# I2C_Servo_v2.net
KiCad netlist of a schematic drawn in EAGLE
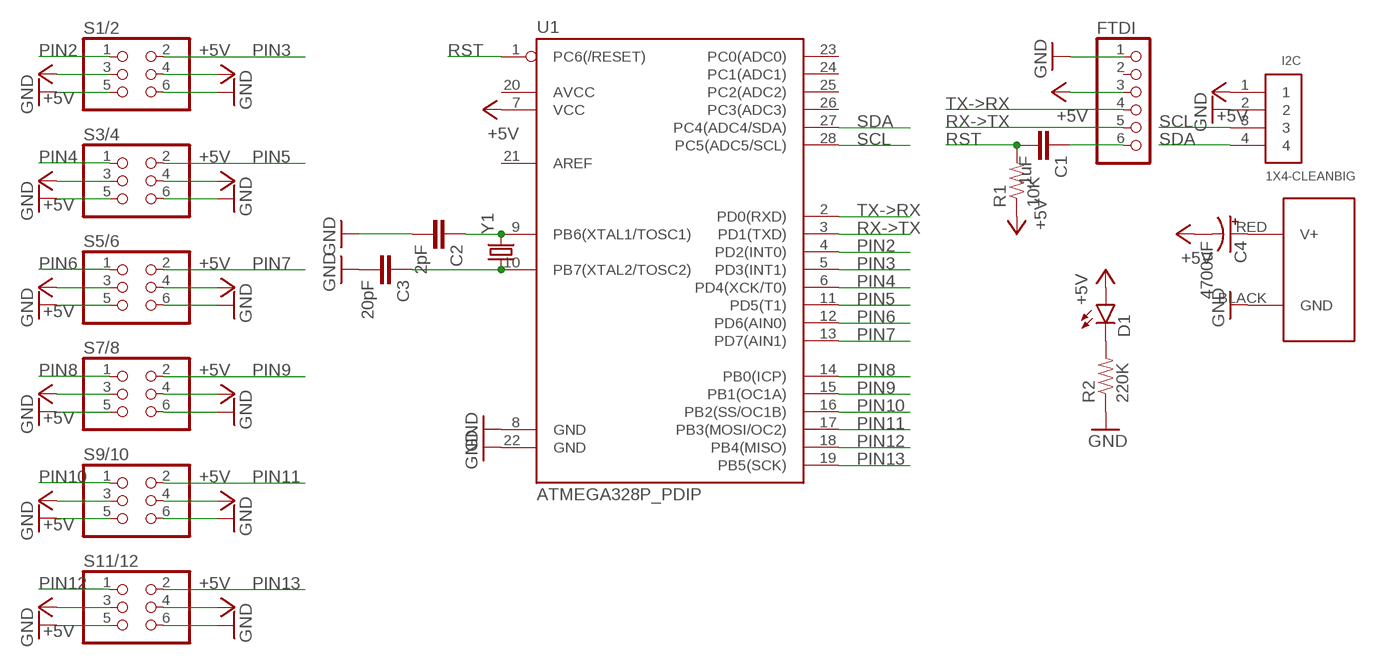
[diagram p0: schematic, sheet 1]

(export (version "E")
  (design (tool "Eeschema 10.0.6"))
  (components
    (comp (ref "C1")
      (value ".1uF")
      (footprint "eagle-import:CAP-PTH-SMALL")
      (libsource (lib "eagle-import") (part "CAPPTH"))
    )
    (comp (ref "C2")
      (value "2pF")
      (footprint "eagle-import:CAP-PTH-SMALL")
      (libsource (lib "eagle-import") (part "CAPPTH"))
    )
    (comp (ref "C3")
      (value "20pF")
      (footprint "eagle-import:CAP-PTH-SMALL")
      (libsource (lib "eagle-import") (part "CAPPTH"))
    )
    (comp (ref "C4")
      (value "4700uF")
      (footprint "eagle-import:E5-13")
      (libsource (lib "eagle-import") (part "CPOL-USE5-13"))
    )
    (comp (ref "D1")
      (value "LED3MM")
      (footprint "eagle-import:LED3MM")
      (libsource (lib "eagle-import") (part "LED3MM"))
    )
    (comp (ref "FTDI")
      (value "PINHD-1X6CLEAN")
      (footprint "eagle-import:1X06-CLEAN")
      (libsource (lib "eagle-import") (part "PINHD-1X6CLEAN"))
    )
    (comp (ref "I2C")
      (value "1X4-CLEANBIG")
      (footprint "eagle-import:1X04-CLEANBIG")
      (libsource (lib "eagle-import") (part "1X4-CLEANBIG"))
    )
    (comp (ref "J1")
      (value "POWERPOLE_POWER25A_HORIZONTAL_G2")
      (footprint "eagle-import:POWERPOLE_PAIR_25A_HORIZ_G2")
      (libsource (lib "eagle-import") (part "POWERPOLE_POWER25A_HORIZONTAL_G2"))
    )
    (comp (ref "R1")
      (value "10K")
      (footprint "eagle-import:AXIAL-0.3")
      (libsource (lib "eagle-import") (part "RESISTORAXIAL-0.3"))
    )
    (comp (ref "R2")
      (value "220K")
      (footprint "eagle-import:AXIAL-0.3")
      (libsource (lib "eagle-import") (part "RESISTORAXIAL-0.3"))
    )
    (comp (ref "S1/2")
      (value "PINHD-2X3")
      (footprint "eagle-import:2X03")
      (libsource (lib "eagle-import") (part "PINHD-2X3"))
    )
    (comp (ref "S3/4")
      (value "PINHD-2X3")
      (footprint "eagle-import:2X03")
      (libsource (lib "eagle-import") (part "PINHD-2X3"))
    )
    (comp (ref "S5/6")
      (value "PINHD-2X3")
      (footprint "eagle-import:2X03")
      (libsource (lib "eagle-import") (part "PINHD-2X3"))
    )
    (comp (ref "S7/8")
      (value "PINHD-2X3")
      (footprint "eagle-import:2X03")
      (libsource (lib "eagle-import") (part "PINHD-2X3"))
    )
    (comp (ref "S9/10")
      (value "PINHD-2X3")
      (footprint "eagle-import:2X03")
      (libsource (lib "eagle-import") (part "PINHD-2X3"))
    )
    (comp (ref "S11/12")
      (value "PINHD-2X3")
      (footprint "eagle-import:2X03")
      (libsource (lib "eagle-import") (part "PINHD-2X3"))
    )
    (comp (ref "U1")
      (value "ATMEGA328P_PDIP")
      (footprint "eagle-import:DIL28-3")
      (libsource (lib "eagle-import") (part "ATMEGA328P_PDIP"))
    )
    (comp (ref "Y1")
      (value "CRYSTALHC49US")
      (footprint "eagle-import:HC49US")
      (libsource (lib "eagle-import") (part "CRYSTALHC49US"))
    )
  )
  (nets
    (net (code "1") (name "+5V") (class "Default")
      (node (ref "C4") (pin "-") (pinfunction "-_-") (pintype "passive"))
      (node (ref "D1") (pin "A") (pinfunction "A_A") (pintype "passive"))
      (node (ref "FTDI") (pin "3") (pinfunction "3_3") (pintype "passive"))
      (node (ref "I2C") (pin "1") (pinfunction "1_1") (pintype "bidirectional"))
      (node (ref "R1") (pin "P$1") (pinfunction "1_P$1") (pintype "passive"))
      (node (ref "S1/2") (pin "3") (pinfunction "3_3") (pintype "passive"))
      (node (ref "S1/2") (pin "4") (pinfunction "4_4") (pintype "passive"))
      (node (ref "S11/12") (pin "3") (pinfunction "3_3") (pintype "passive"))
      (node (ref "S11/12") (pin "4") (pinfunction "4_4") (pintype "passive"))
      (node (ref "S3/4") (pin "3") (pinfunction "3_3") (pintype "passive"))
      (node (ref "S3/4") (pin "4") (pinfunction "4_4") (pintype "passive"))
      (node (ref "S5/6") (pin "3") (pinfunction "3_3") (pintype "passive"))
      (node (ref "S5/6") (pin "4") (pinfunction "4_4") (pintype "passive"))
      (node (ref "S7/8") (pin "3") (pinfunction "3_3") (pintype "passive"))
      (node (ref "S7/8") (pin "4") (pinfunction "4_4") (pintype "passive"))
      (node (ref "S9/10") (pin "3") (pinfunction "3_3") (pintype "passive"))
      (node (ref "S9/10") (pin "4") (pinfunction "4_4") (pintype "passive"))
      (node (ref "U1") (pin "7") (pinfunction "VCC_7") (pintype "bidirectional"))
    )
    (net (code "2") (name "/PIN2") (class "Default")
      (node (ref "S1/2") (pin "1") (pinfunction "1_1") (pintype "passive"))
      (node (ref "U1") (pin "4") (pinfunction "PD2(INT0)_4") (pintype "bidirectional"))
    )
    (net (code "3") (name "/PIN3") (class "Default")
      (node (ref "S1/2") (pin "2") (pinfunction "2_2") (pintype "passive"))
      (node (ref "U1") (pin "5") (pinfunction "PD3(INT1)_5") (pintype "bidirectional"))
    )
    (net (code "4") (name "/PIN4") (class "Default")
      (node (ref "S3/4") (pin "1") (pinfunction "1_1") (pintype "passive"))
      (node (ref "U1") (pin "6") (pinfunction "PD4(XCK/T0)_6") (pintype "bidirectional"))
    )
    (net (code "5") (name "/PIN5") (class "Default")
      (node (ref "S3/4") (pin "2") (pinfunction "2_2") (pintype "passive"))
      (node (ref "U1") (pin "11") (pinfunction "PD5(T1)_11") (pintype "bidirectional"))
    )
    (net (code "6") (name "/PIN6") (class "Default")
      (node (ref "S5/6") (pin "1") (pinfunction "1_1") (pintype "passive"))
      (node (ref "U1") (pin "12") (pinfunction "PD6(AIN0)_12") (pintype "bidirectional"))
    )
    (net (code "7") (name "/PIN7") (class "Default")
      (node (ref "S5/6") (pin "2") (pinfunction "2_2") (pintype "passive"))
      (node (ref "U1") (pin "13") (pinfunction "PD7(AIN1)_13") (pintype "bidirectional"))
    )
    (net (code "8") (name "/PIN8") (class "Default")
      (node (ref "S7/8") (pin "1") (pinfunction "1_1") (pintype "passive"))
      (node (ref "U1") (pin "14") (pinfunction "PB0(ICP)_14") (pintype "bidirectional"))
    )
    (net (code "9") (name "/PIN9") (class "Default")
      (node (ref "S7/8") (pin "2") (pinfunction "2_2") (pintype "passive"))
      (node (ref "U1") (pin "15") (pinfunction "PB1(OC1A)_15") (pintype "bidirectional"))
    )
    (net (code "10") (name "/PIN10") (class "Default")
      (node (ref "S9/10") (pin "1") (pinfunction "1_1") (pintype "passive"))
      (node (ref "U1") (pin "16") (pinfunction "PB2(SS/OC1B)_16") (pintype "bidirectional"))
    )
    (net (code "11") (name "/PIN11") (class "Default")
      (node (ref "S9/10") (pin "2") (pinfunction "2_2") (pintype "passive"))
      (node (ref "U1") (pin "17") (pinfunction "PB3(MOSI/OC2)_17") (pintype "bidirectional"))
    )
    (net (code "12") (name "/PIN12") (class "Default")
      (node (ref "S11/12") (pin "1") (pinfunction "1_1") (pintype "passive"))
      (node (ref "U1") (pin "18") (pinfunction "PB4(MISO)_18") (pintype "bidirectional"))
    )
    (net (code "13") (name "/PIN13") (class "Default")
      (node (ref "S11/12") (pin "2") (pinfunction "2_2") (pintype "passive"))
      (node (ref "U1") (pin "19") (pinfunction "PB5(SCK)_19") (pintype "bidirectional"))
    )
    (net (code "14") (name "/RST") (class "Default")
      (node (ref "C1") (pin "2") (pinfunction "2_2") (pintype "passive"))
      (node (ref "R1") (pin "P$2") (pinfunction "2_P$2") (pintype "passive"))
      (node (ref "U1") (pin "1") (pinfunction "PC6(/RESET)_1") (pintype "bidirectional"))
    )
    (net (code "15") (name "/RX->TX") (class "Default")
      (node (ref "FTDI") (pin "5") (pinfunction "5_5") (pintype "passive"))
      (node (ref "U1") (pin "3") (pinfunction "PD1(TXD)_3") (pintype "bidirectional"))
    )
    (net (code "16") (name "/SCL") (class "Default")
      (node (ref "I2C") (pin "3") (pinfunction "3_3") (pintype "bidirectional"))
      (node (ref "U1") (pin "28") (pinfunction "PC5(ADC5/SCL)_28") (pintype "bidirectional"))
    )
    (net (code "17") (name "/SDA") (class "Default")
      (node (ref "I2C") (pin "4") (pinfunction "4_4") (pintype "bidirectional"))
      (node (ref "U1") (pin "27") (pinfunction "PC4(ADC4/SDA)_27") (pintype "bidirectional"))
    )
    (net (code "18") (name "/TX->RX") (class "Default")
      (node (ref "FTDI") (pin "4") (pinfunction "4_4") (pintype "passive"))
      (node (ref "U1") (pin "2") (pinfunction "PD0(RXD)_2") (pintype "bidirectional"))
    )
    (net (code "19") (name "GND") (class "Default")
      (node (ref "C2") (pin "2") (pinfunction "2_2") (pintype "passive"))
      (node (ref "C3") (pin "2") (pinfunction "2_2") (pintype "passive"))
      (node (ref "FTDI") (pin "1") (pinfunction "1_1") (pintype "passive"))
      (node (ref "I2C") (pin "2") (pinfunction "2_2") (pintype "bidirectional"))
      (node (ref "J1") (pin "BLACK") (pinfunction "GND_BLACK") (pintype "power_in"))
      (node (ref "R2") (pin "P$1") (pinfunction "1_P$1") (pintype "passive"))
      (node (ref "S1/2") (pin "5") (pinfunction "5_5") (pintype "passive"))
      (node (ref "S1/2") (pin "6") (pinfunction "6_6") (pintype "passive"))
      (node (ref "S11/12") (pin "5") (pinfunction "5_5") (pintype "passive"))
      (node (ref "S11/12") (pin "6") (pinfunction "6_6") (pintype "passive"))
      (node (ref "S3/4") (pin "5") (pinfunction "5_5") (pintype "passive"))
      (node (ref "S3/4") (pin "6") (pinfunction "6_6") (pintype "passive"))
      (node (ref "S5/6") (pin "5") (pinfunction "5_5") (pintype "passive"))
      (node (ref "S5/6") (pin "6") (pinfunction "6_6") (pintype "passive"))
      (node (ref "S7/8") (pin "5") (pinfunction "5_5") (pintype "passive"))
      (node (ref "S7/8") (pin "6") (pinfunction "6_6") (pintype "passive"))
      (node (ref "S9/10") (pin "5") (pinfunction "5_5") (pintype "passive"))
      (node (ref "S9/10") (pin "6") (pinfunction "6_6") (pintype "passive"))
      (node (ref "U1") (pin "22") (pinfunction "GND_22") (pintype "bidirectional"))
      (node (ref "U1") (pin "8") (pinfunction "GND_8") (pintype "bidirectional"))
    )
    (net (code "20") (name "Net-(C1-Pad1)") (class "Default")
      (node (ref "C1") (pin "1") (pinfunction "1_1") (pintype "passive"))
      (node (ref "FTDI") (pin "6") (pinfunction "6_6") (pintype "passive"))
    )
    (net (code "21") (name "Net-(D1-C)") (class "Default")
      (node (ref "D1") (pin "K") (pinfunction "C_K") (pintype "passive"))
      (node (ref "R2") (pin "P$2") (pinfunction "2_P$2") (pintype "passive"))
    )
    (net (code "22") (name "Net-(J1-V+)") (class "Default")
      (node (ref "C4") (pin "+") (pinfunction "+_+") (pintype "passive"))
      (node (ref "J1") (pin "RED") (pinfunction "V+_RED") (pintype "power_in"))
    )
    (net (code "23") (name "Net-(U1-PB6(XTAL1{slash}TOSC1))") (class "Default")
      (node (ref "C2") (pin "1") (pinfunction "1_1") (pintype "passive"))
      (node (ref "U1") (pin "9") (pinfunction "PB6(XTAL1/TOSC1)_9") (pintype "bidirectional"))
      (node (ref "Y1") (pin "2") (pinfunction "2_2") (pintype "passive"))
    )
    (net (code "24") (name "Net-(U1-PB7(XTAL2{slash}TOSC2))") (class "Default")
      (node (ref "C3") (pin "1") (pinfunction "1_1") (pintype "passive"))
      (node (ref "U1") (pin "10") (pinfunction "PB7(XTAL2/TOSC2)_10") (pintype "bidirectional"))
      (node (ref "Y1") (pin "1") (pinfunction "1_1") (pintype "passive"))
    )
    (net (code "25") (name "unconnected-(FTDI-Pad2)") (class "Default")
      (node (ref "FTDI") (pin "2") (pinfunction "2_2") (pintype "passive"))
    )
    (net (code "26") (name "unconnected-(U1-AREF-Pad21)") (class "Default")
      (node (ref "U1") (pin "21") (pinfunction "AREF_21") (pintype "bidirectional"))
    )
    (net (code "27") (name "unconnected-(U1-AVCC-Pad20)") (class "Default")
      (node (ref "U1") (pin "20") (pinfunction "AVCC_20") (pintype "bidirectional"))
    )
    (net (code "28") (name "unconnected-(U1-PC0(ADC0)-Pad23)") (class "Default")
      (node (ref "U1") (pin "23") (pinfunction "PC0(ADC0)_23") (pintype "bidirectional"))
    )
    (net (code "29") (name "unconnected-(U1-PC1(ADC1)-Pad24)") (class "Default")
      (node (ref "U1") (pin "24") (pinfunction "PC1(ADC1)_24") (pintype "bidirectional"))
    )
    (net (code "30") (name "unconnected-(U1-PC2(ADC2)-Pad25)") (class "Default")
      (node (ref "U1") (pin "25") (pinfunction "PC2(ADC2)_25") (pintype "bidirectional"))
    )
    (net (code "31") (name "unconnected-(U1-PC3(ADC3)-Pad26)") (class "Default")
      (node (ref "U1") (pin "26") (pinfunction "PC3(ADC3)_26") (pintype "bidirectional"))
    )
  )
)
